# V1_0.net
KiCad netlist of a schematic drawn in Altium Designer
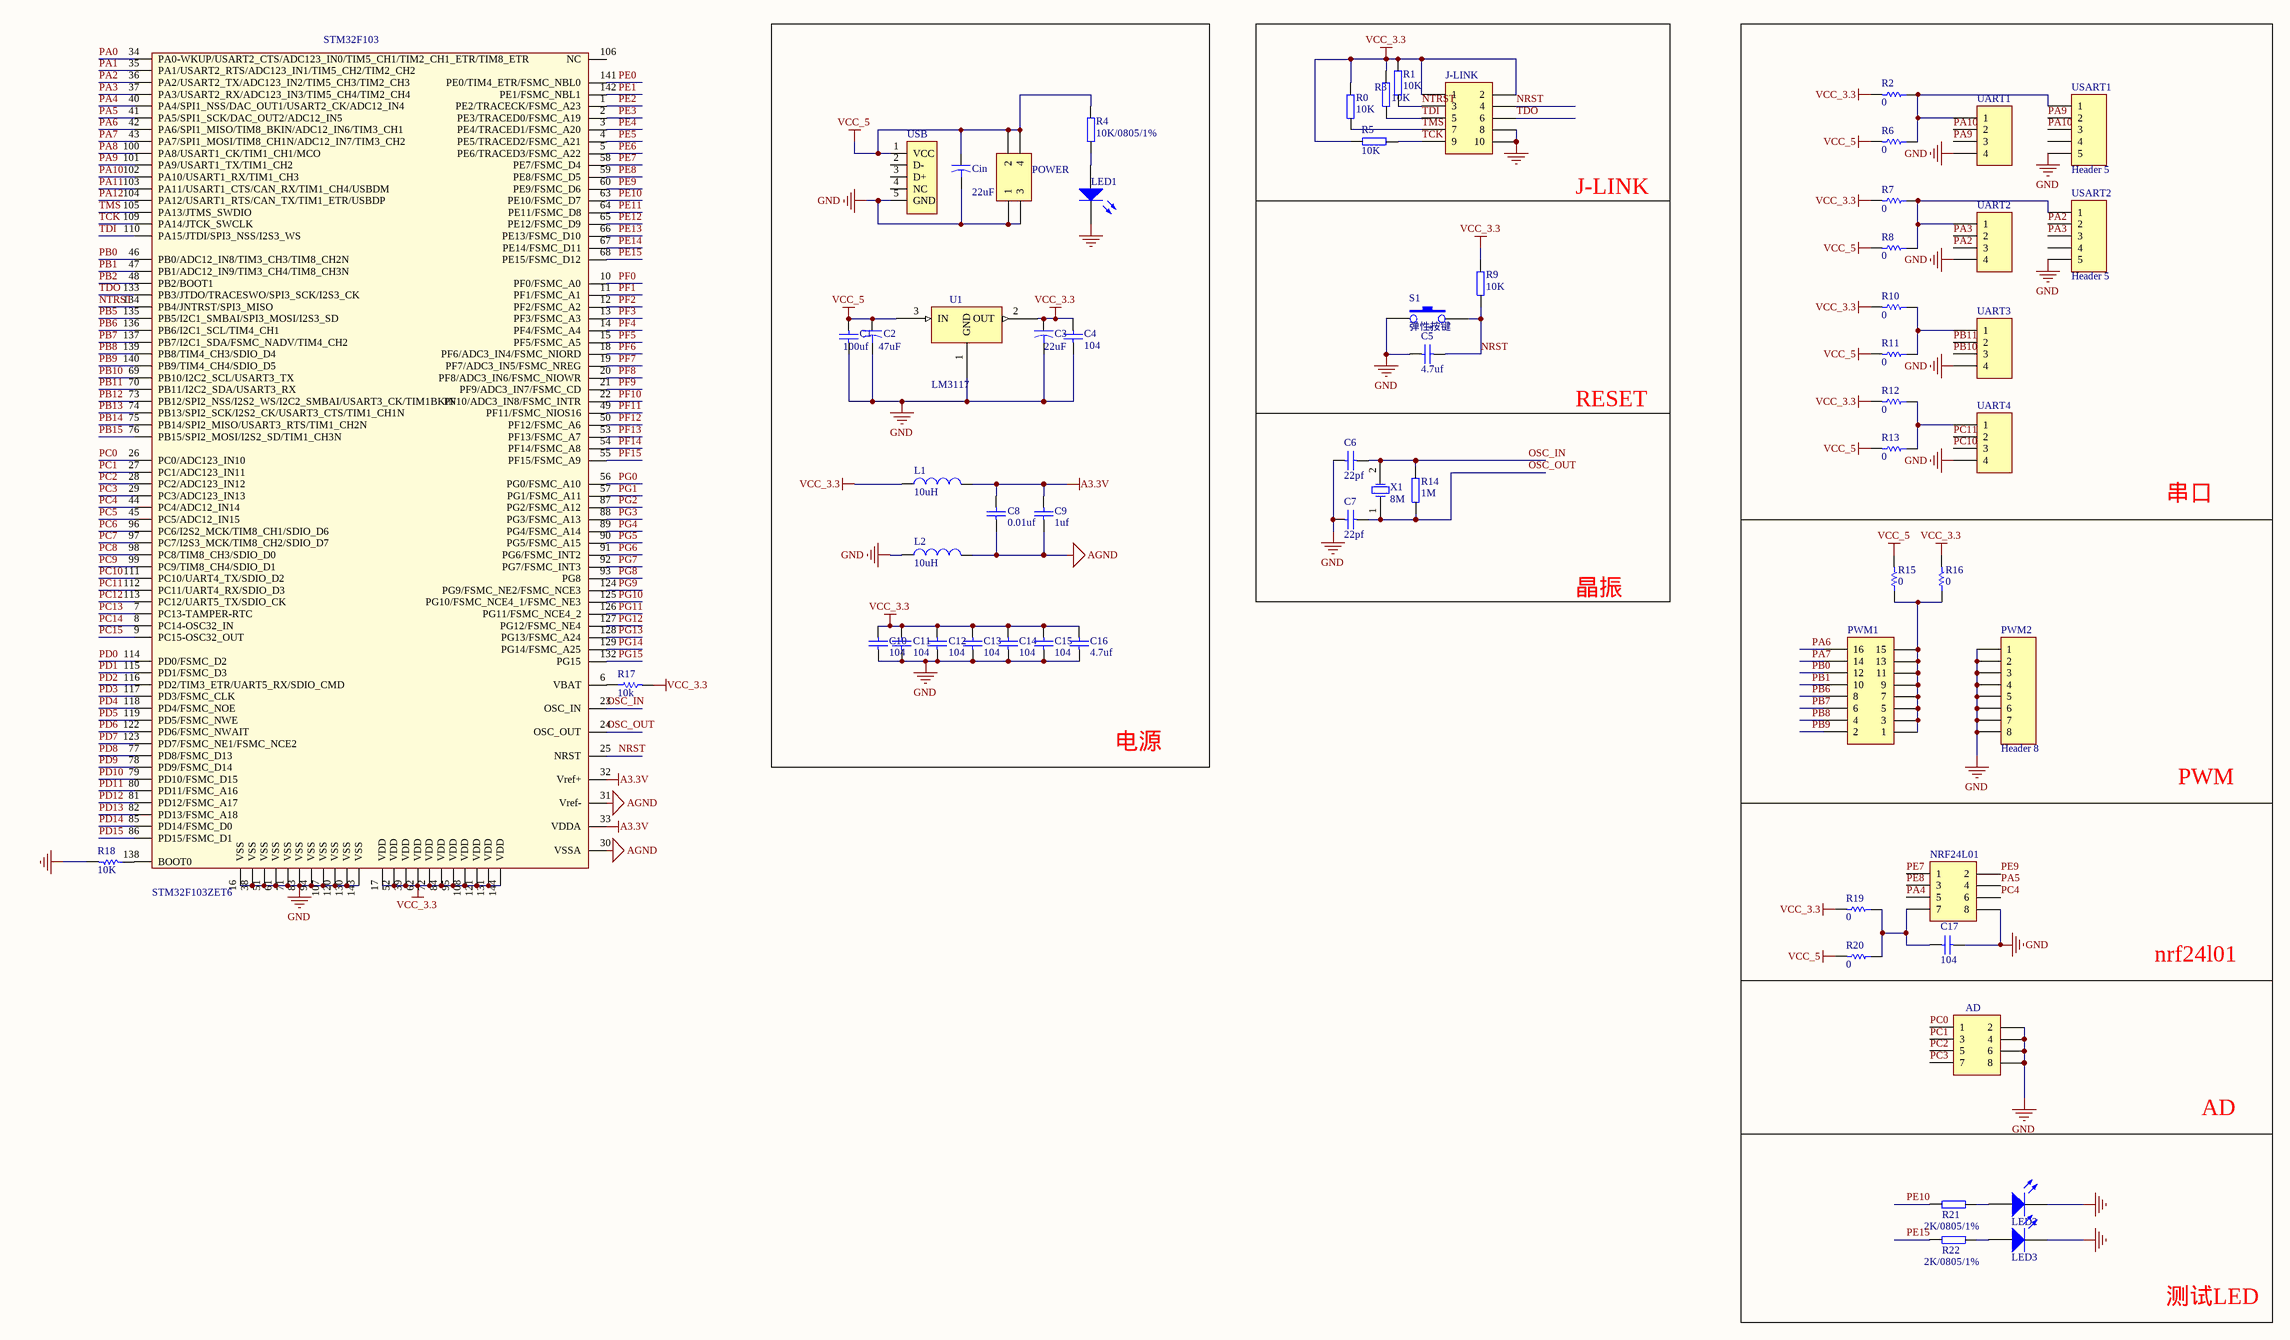
[diagram p0: 解析板V1.0.SchDoc]

(export (version "E")
  (design (tool "Eeschema 10.0.6"))
  (components
    (comp (ref "AD")
      (value "Header 4X2")
      (footprint "HDR2X4")
      (description "Header, 4-Pin, Dual row")
      (fields (field (name "PUBLISHER") "Altium Limited"))
      (libsource (lib "Miscellaneous Connectors") (part "Header 4X2"))
    )
    (comp (ref "C1")
      (value "100uf")
      (footprint "0805")
      (description "C0805")
      (fields (field (name "Comment") "0805"))
      (libsource (lib "MyLib") (part "Cap C0805"))
    )
    (comp (ref "C2")
      (value "47uF")
      (footprint "1812")
      (description "Capacitor")
      (fields (field (name "Comment") "Cap2") (field (name "PUBLISHER") "Altium Limited"))
      (libsource (lib "Miscellaneous Devices") (part "Cap2"))
    )
    (comp (ref "C3")
      (value "22uF")
      (footprint "1812")
      (description "Capacitor")
      (fields (field (name "Comment") "Cap2") (field (name "PUBLISHER") "Altium Limited"))
      (libsource (lib "Miscellaneous Devices") (part "Cap2"))
    )
    (comp (ref "C4")
      (value "104")
      (footprint "0805")
      (description "C0805")
      (fields (field (name "Comment") "0805"))
      (libsource (lib "MyLib") (part "Cap C0805"))
    )
    (comp (ref "C5")
      (value "4.7uf")
      (footprint "0805")
      (description "C0805")
      (fields (field (name "Comment") "0805"))
      (libsource (lib "MyLib") (part "Cap C0805"))
    )
    (comp (ref "C6")
      (value "22pf")
      (footprint "0805")
      (description "C0805")
      (fields (field (name "Comment") "0805"))
      (libsource (lib "MyLib") (part "Cap C0805"))
    )
    (comp (ref "C7")
      (value "22pf")
      (footprint "0805")
      (description "C0805")
      (fields (field (name "Comment") "0805"))
      (libsource (lib "MyLib") (part "Cap C0805"))
    )
    (comp (ref "C8")
      (value "0.01uf")
      (footprint "0805")
      (description "C0805")
      (fields (field (name "Comment") "0805"))
      (libsource (lib "MyLib") (part "Cap C0805"))
    )
    (comp (ref "C9")
      (value "1uf")
      (footprint "0805")
      (description "C0805")
      (fields (field (name "Comment") "0805"))
      (libsource (lib "MyLib") (part "Cap C0805"))
    )
    (comp (ref "C10")
      (value "104")
      (footprint "0805")
      (description "C0805")
      (fields (field (name "Comment") "0805"))
      (libsource (lib "MyLib") (part "Cap C0805"))
    )
    (comp (ref "C11")
      (value "104")
      (footprint "0805")
      (description "C0805")
      (fields (field (name "Comment") "0805"))
      (libsource (lib "MyLib") (part "Cap C0805"))
    )
    (comp (ref "C12")
      (value "104")
      (footprint "0805")
      (description "C0805")
      (fields (field (name "Comment") "0805"))
      (libsource (lib "MyLib") (part "Cap C0805"))
    )
    (comp (ref "C13")
      (value "104")
      (footprint "0805")
      (description "C0805")
      (fields (field (name "Comment") "0805"))
      (libsource (lib "MyLib") (part "Cap C0805"))
    )
    (comp (ref "C14")
      (value "104")
      (footprint "0805")
      (description "C0805")
      (fields (field (name "Comment") "0805"))
      (libsource (lib "MyLib") (part "Cap C0805"))
    )
    (comp (ref "C15")
      (value "104")
      (footprint "0805")
      (description "C0805")
      (fields (field (name "Comment") "0805"))
      (libsource (lib "MyLib") (part "Cap C0805"))
    )
    (comp (ref "C16")
      (value "4.7uf")
      (footprint "0805")
      (description "C0805")
      (fields (field (name "Comment") "0805"))
      (libsource (lib "MyLib") (part "Cap C0805"))
    )
    (comp (ref "C17")
      (value "104")
      (footprint "0805")
      (description "C0805")
      (fields (field (name "Comment") "0805"))
      (libsource (lib "MyLib") (part "Cap C0805"))
    )
    (comp (ref "Cin")
      (value "22uF")
      (footprint "1812")
      (description "Capacitor")
      (fields (field (name "Comment") "Cap2") (field (name "PUBLISHER") "Altium Limited"))
      (libsource (lib "Miscellaneous Devices") (part "Cap2"))
    )
    (comp (ref "J-LINK")
      (value "Header 5X2")
      (footprint "HDR2X5")
      (description "Header, 5-Pin, Dual row")
      (fields (field (name "PUBLISHER") "Altium Limited"))
      (libsource (lib "Miscellaneous Connectors") (part "Header 5X2"))
    )
    (comp (ref "L1")
      (value "10uH")
      (footprint "0805")
      (description "Inductor")
      (fields (field (name "PUBLISHER") "Altium Limited"))
      (libsource (lib "Miscellaneous Devices") (part "Inductor"))
    )
    (comp (ref "L2")
      (value "10uH")
      (footprint "0805")
      (description "Inductor")
      (fields (field (name "PUBLISHER") "Altium Limited"))
      (libsource (lib "Miscellaneous Devices") (part "Inductor"))
    )
    (comp (ref "LED1") (value "LED") (footprint "0805") (libsource (lib "K60") (part "LED")))
    (comp (ref "LED2") (value "LED") (footprint "0805") (libsource (lib "K60") (part "LED")))
    (comp (ref "LED3") (value "LED") (footprint "0805") (libsource (lib "K60") (part "LED")))
    (comp (ref "NRF24L01")
      (value "Header 4X2")
      (footprint "HDR2X4")
      (description "Header, 4-Pin, Dual row")
      (fields (field (name "PUBLISHER") "Altium Limited"))
      (libsource (lib "Miscellaneous Connectors") (part "Header 4X2"))
    )
    (comp (ref "POWER")
      (value "Header 2X2")
      (footprint "HDR2X2")
      (description "Header, 2-Pin, Dual row")
      (fields (field (name "PUBLISHER") "Altium Limited"))
      (libsource (lib "Miscellaneous Connectors") (part "Header 2X2"))
    )
    (comp (ref "PWM1")
      (value "Header 8X2")
      (footprint "HDR2X8")
      (description "Header, 8-Pin, Dual row")
      (fields (field (name "PUBLISHER") "Altium Limited"))
      (libsource (lib "Miscellaneous Connectors") (part "Header 8X2"))
    )
    (comp (ref "PWM2")
      (value "Header 8")
      (footprint "HDR1X8")
      (description "Header, 8-Pin")
      (fields (field (name "PUBLISHER") "Altium Limited"))
      (libsource (lib "Miscellaneous Connectors") (part "Header 8"))
    )
    (comp (ref "R0") (value "10K") (footprint "0805") (libsource (lib "*") (part "RES5")))
    (comp (ref "R1") (value "10K") (footprint "0805") (libsource (lib "*") (part "RES5")))
    (comp (ref "R2")
      (value "0")
      (footprint "0805")
      (description "Resistor")
      (fields (field (name "Comment") "Res1") (field (name "PUBLISHER") "Altium Limited"))
      (libsource (lib "Miscellaneous Devices") (part "Res1"))
    )
    (comp (ref "R3") (value "10K") (footprint "0805") (libsource (lib "*") (part "RES5")))
    (comp (ref "R4") (value "10K/0805/1%") (footprint "0805") (libsource (lib "*") (part "RES5")))
    (comp (ref "R5") (value "10K") (footprint "0805") (libsource (lib "*") (part "RES5")))
    (comp (ref "R6")
      (value "0")
      (footprint "0805")
      (description "Resistor")
      (fields (field (name "Comment") "Res1") (field (name "PUBLISHER") "Altium Limited"))
      (libsource (lib "Miscellaneous Devices") (part "Res1"))
    )
    (comp (ref "R7")
      (value "0")
      (footprint "0805")
      (description "Resistor")
      (fields (field (name "Comment") "Res1") (field (name "PUBLISHER") "Altium Limited"))
      (libsource (lib "Miscellaneous Devices") (part "Res1"))
    )
    (comp (ref "R8")
      (value "0")
      (footprint "0805")
      (description "Resistor")
      (fields (field (name "Comment") "Res1") (field (name "PUBLISHER") "Altium Limited"))
      (libsource (lib "Miscellaneous Devices") (part "Res1"))
    )
    (comp (ref "R9") (value "10K") (footprint "0805") (libsource (lib "*") (part "RES5")))
    (comp (ref "R10")
      (value "0")
      (footprint "0805")
      (description "Resistor")
      (fields (field (name "Comment") "Res1") (field (name "PUBLISHER") "Altium Limited"))
      (libsource (lib "Miscellaneous Devices") (part "Res1"))
    )
    (comp (ref "R11")
      (value "0")
      (footprint "0805")
      (description "Resistor")
      (fields (field (name "Comment") "Res1") (field (name "PUBLISHER") "Altium Limited"))
      (libsource (lib "Miscellaneous Devices") (part "Res1"))
    )
    (comp (ref "R12")
      (value "0")
      (footprint "0805")
      (description "Resistor")
      (fields (field (name "Comment") "Res1") (field (name "PUBLISHER") "Altium Limited"))
      (libsource (lib "Miscellaneous Devices") (part "Res1"))
    )
    (comp (ref "R13")
      (value "0")
      (footprint "0805")
      (description "Resistor")
      (fields (field (name "Comment") "Res1") (field (name "PUBLISHER") "Altium Limited"))
      (libsource (lib "Miscellaneous Devices") (part "Res1"))
    )
    (comp (ref "R14") (value "1M") (footprint "0805") (libsource (lib "*") (part "RES5")))
    (comp (ref "R15")
      (value "0")
      (footprint "0805")
      (description "Resistor")
      (fields (field (name "Comment") "Res1") (field (name "PUBLISHER") "Altium Limited"))
      (libsource (lib "Miscellaneous Devices") (part "Res1"))
    )
    (comp (ref "R16")
      (value "0")
      (footprint "0805")
      (description "Resistor")
      (fields (field (name "Comment") "Res1") (field (name "PUBLISHER") "Altium Limited"))
      (libsource (lib "Miscellaneous Devices") (part "Res1"))
    )
    (comp (ref "R17")
      (value "10k")
      (footprint "0805")
      (description "Resistor")
      (fields (field (name "Comment") "Res1") (field (name "PUBLISHER") "Altium Limited"))
      (libsource (lib "Miscellaneous Devices") (part "Res1"))
    )
    (comp (ref "R18")
      (value "10K")
      (footprint "0805")
      (description "Resistor")
      (fields (field (name "PUBLISHER") "Altium Limited"))
      (libsource (lib "*") (part "res1"))
    )
    (comp (ref "R19")
      (value "0")
      (footprint "0805")
      (description "Resistor")
      (fields (field (name "Comment") "Res1") (field (name "PUBLISHER") "Altium Limited"))
      (libsource (lib "Miscellaneous Devices") (part "Res1"))
    )
    (comp (ref "R20")
      (value "0")
      (footprint "0805")
      (description "Resistor")
      (fields (field (name "Comment") "Res1") (field (name "PUBLISHER") "Altium Limited"))
      (libsource (lib "Miscellaneous Devices") (part "Res1"))
    )
    (comp (ref "R21") (value "2K/0805/1%") (footprint "0805") (libsource (lib "*") (part "RES5")))
    (comp (ref "R22") (value "2K/0805/1%") (footprint "0805") (libsource (lib "*") (part "RES5")))
    (comp (ref "S1")
      (value "*")
      (footprint "按键开关（贴片）")
      (fields (field (name "COMM") "弹性按键"))
      (libsource (lib "Integrated_Library1") (part "单弹性按键"))
    )
    (comp (ref "STM32F103")
      (value "STM32F103ZET6")
      (footprint "LQFP144")
      (libsource (lib "WARSHIP") (part "STM32F103ZET6"))
    )
    (comp (ref "U1")
      (value "LM3117")
      (footprint "LM1117")
      (libsource (lib "Integrated_Library1") (part "LM1117"))
    )
    (comp (ref "UART1")
      (value "Header 4")
      (footprint "HDR1X4")
      (description "Header, 4-Pin")
      (fields (field (name "PUBLISHER") "Altium Limited"))
      (libsource (lib "Miscellaneous Connectors") (part "Header 4"))
    )
    (comp (ref "UART2")
      (value "Header 4")
      (footprint "HDR1X4")
      (description "Header, 4-Pin")
      (fields (field (name "PUBLISHER") "Altium Limited"))
      (libsource (lib "Miscellaneous Connectors") (part "Header 4"))
    )
    (comp (ref "UART3")
      (value "Header 4")
      (footprint "HDR1X4")
      (description "Header, 4-Pin")
      (fields (field (name "PUBLISHER") "Altium Limited"))
      (libsource (lib "Miscellaneous Connectors") (part "Header 4"))
    )
    (comp (ref "UART4")
      (value "Header 4")
      (footprint "HDR1X4")
      (description "Header, 4-Pin")
      (fields (field (name "PUBLISHER") "Altium Limited"))
      (libsource (lib "Miscellaneous Connectors") (part "Header 4"))
    )
    (comp (ref "USART1")
      (value "Header 5")
      (footprint "HDR1X5")
      (description "Header, 5-Pin")
      (fields (field (name "PUBLISHER") "Altium Limited"))
      (libsource (lib "Miscellaneous Connectors") (part "Header 5"))
    )
    (comp (ref "USART2")
      (value "Header 5")
      (footprint "HDR1X5")
      (description "Header, 5-Pin")
      (fields (field (name "PUBLISHER") "Altium Limited"))
      (libsource (lib "Miscellaneous Connectors") (part "Header 5"))
    )
    (comp (ref "USB") (value "USB-B(Mini)") (footprint "USB/SM0.8-6H5") (libsource (lib "原理图") (part "USB5")))
    (comp (ref "X1") (value "8M") (footprint "0.5-晶振") (libsource (lib "Integrated_Library1") (part "XTAL")))
  )
  (nets
    (net (code "1") (name "/NRST") (class "Default")
      (node (ref "C5") (pin "1") (pinfunction "1_1") (pintype "passive"))
      (node (ref "J-LINK") (pin "4") (pinfunction "4_4") (pintype "passive"))
      (node (ref "R9") (pin "1") (pintype "passive"))
      (node (ref "S1") (pin "2") (pinfunction "2_2") (pintype "passive"))
      (node (ref "STM32F103") (pin "25") (pinfunction "NRST_25") (pintype "passive"))
    )
    (net (code "2") (name "/NTRST") (class "Default")
      (node (ref "J-LINK") (pin "3") (pinfunction "3_3") (pintype "passive"))
      (node (ref "R1") (pin "1") (pintype "passive"))
      (node (ref "STM32F103") (pin "134") (pinfunction "PB4/JNTRST/SPI3_MISO_134") (pintype "passive"))
    )
    (net (code "3") (name "/OSC_IN") (class "Default")
      (node (ref "C6") (pin "1") (pinfunction "1_1") (pintype "passive"))
      (node (ref "R14") (pin "2") (pintype "passive"))
      (node (ref "STM32F103") (pin "23") (pinfunction "OSC_IN_23") (pintype "passive"))
      (node (ref "X1") (pin "2") (pinfunction "OSC2_2") (pintype "passive"))
    )
    (net (code "4") (name "/OSC_OUT") (class "Default")
      (node (ref "C7") (pin "1") (pinfunction "1_1") (pintype "passive"))
      (node (ref "R14") (pin "1") (pintype "passive"))
      (node (ref "STM32F103") (pin "24") (pinfunction "OSC_OUT_24") (pintype "passive"))
      (node (ref "X1") (pin "1") (pinfunction "OSC1_1") (pintype "passive"))
    )
    (net (code "5") (name "/PA0") (class "Default")
      (node (ref "STM32F103") (pin "34") (pinfunction "PA0-WKUP/USART2_CTS/ADC123_IN0/TIM5_CH1/TIM2_CH1_ETR/TIM8_ETR_34") (pintype "passive"))
    )
    (net (code "6") (name "/PA1") (class "Default")
      (node (ref "STM32F103") (pin "35") (pinfunction "PA1/USART2_RTS/ADC123_IN1/TIM5_CH2/TIM2_CH2_35") (pintype "passive"))
    )
    (net (code "7") (name "/PA2") (class "Default")
      (node (ref "STM32F103") (pin "36") (pinfunction "PA2/USART2_TX/ADC123_IN2/TIM5_CH3/TIM2_CH3_36") (pintype "passive"))
      (node (ref "UART2") (pin "3") (pinfunction "3_3") (pintype "passive"))
      (node (ref "USART2") (pin "2") (pinfunction "2_2") (pintype "passive"))
    )
    (net (code "8") (name "/PA3") (class "Default")
      (node (ref "STM32F103") (pin "37") (pinfunction "PA3/USART2_RX/ADC123_IN3/TIM5_CH4/TIM2_CH4_37") (pintype "passive"))
      (node (ref "UART2") (pin "2") (pinfunction "2_2") (pintype "passive"))
      (node (ref "USART2") (pin "3") (pinfunction "3_3") (pintype "passive"))
    )
    (net (code "9") (name "/PA4") (class "Default")
      (node (ref "NRF24L01") (pin "5") (pinfunction "5_5") (pintype "passive"))
      (node (ref "STM32F103") (pin "40") (pinfunction "PA4/SPI1_NSS/DAC_OUT1/USART2_CK/ADC12_IN4_40") (pintype "passive"))
    )
    (net (code "10") (name "/PA5") (class "Default")
      (node (ref "NRF24L01") (pin "4") (pinfunction "4_4") (pintype "passive"))
      (node (ref "STM32F103") (pin "41") (pinfunction "PA5/SPI1_SCK/DAC_OUT2/ADC12_IN5_41") (pintype "passive"))
    )
    (net (code "11") (name "/PA6") (class "Default")
      (node (ref "PWM1") (pin "16") (pinfunction "16_16") (pintype "passive"))
      (node (ref "STM32F103") (pin "42") (pinfunction "PA6/SPI1_MISO/TIM8_BKIN/ADC12_IN6/TIM3_CH1_42") (pintype "passive"))
    )
    (net (code "12") (name "/PA7") (class "Default")
      (node (ref "PWM1") (pin "14") (pinfunction "14_14") (pintype "passive"))
      (node (ref "STM32F103") (pin "43") (pinfunction "PA7/SPI1_MOSI/TIM8_CH1N/ADC12_IN7/TIM3_CH2_43") (pintype "passive"))
    )
    (net (code "13") (name "/PA8") (class "Default")
      (node (ref "STM32F103") (pin "100") (pinfunction "PA8/USART1_CK/TIM1_CH1/MCO_100") (pintype "passive"))
    )
    (net (code "14") (name "/PA9") (class "Default")
      (node (ref "STM32F103") (pin "101") (pinfunction "PA9/USART1_TX/TIM1_CH2_101") (pintype "passive"))
      (node (ref "UART1") (pin "3") (pinfunction "3_3") (pintype "passive"))
      (node (ref "USART1") (pin "2") (pinfunction "2_2") (pintype "passive"))
    )
    (net (code "15") (name "/PA10") (class "Default")
      (node (ref "STM32F103") (pin "102") (pinfunction "PA10/USART1_RX/TIM1_CH3_102") (pintype "passive"))
      (node (ref "UART1") (pin "2") (pinfunction "2_2") (pintype "passive"))
      (node (ref "USART1") (pin "3") (pinfunction "3_3") (pintype "passive"))
    )
    (net (code "16") (name "/PA11") (class "Default")
      (node (ref "STM32F103") (pin "103") (pinfunction "PA11/USART1_CTS/CAN_RX/TIM1_CH4/USBDM_103") (pintype "passive"))
    )
    (net (code "17") (name "/PA12") (class "Default")
      (node (ref "STM32F103") (pin "104") (pinfunction "PA12/USART1_RTS/CAN_TX/TIM1_ETR/USBDP_104") (pintype "passive"))
    )
    (net (code "18") (name "/PB0") (class "Default")
      (node (ref "PWM1") (pin "12") (pinfunction "12_12") (pintype "passive"))
      (node (ref "STM32F103") (pin "46") (pinfunction "PB0/ADC12_IN8/TIM3_CH3/TIM8_CH2N_46") (pintype "passive"))
    )
    (net (code "19") (name "/PB1") (class "Default")
      (node (ref "PWM1") (pin "10") (pinfunction "10_10") (pintype "passive"))
      (node (ref "STM32F103") (pin "47") (pinfunction "PB1/ADC12_IN9/TIM3_CH4/TIM8_CH3N_47") (pintype "passive"))
    )
    (net (code "20") (name "/PB2") (class "Default")
      (node (ref "STM32F103") (pin "48") (pinfunction "PB2/BOOT1_48") (pintype "passive"))
    )
    (net (code "21") (name "/PB5") (class "Default")
      (node (ref "STM32F103") (pin "135") (pinfunction "PB5/I2C1_SMBAI/SPI3_MOSI/I2S3_SD_135") (pintype "passive"))
    )
    (net (code "22") (name "/PB6") (class "Default")
      (node (ref "PWM1") (pin "8") (pinfunction "8_8") (pintype "passive"))
      (node (ref "STM32F103") (pin "136") (pinfunction "PB6/I2C1_SCL/TIM4_CH1_136") (pintype "passive"))
    )
    (net (code "23") (name "/PB7") (class "Default")
      (node (ref "PWM1") (pin "6") (pinfunction "6_6") (pintype "passive"))
      (node (ref "STM32F103") (pin "137") (pinfunction "PB7/I2C1_SDA/FSMC_NADV/TIM4_CH2_137") (pintype "passive"))
    )
    (net (code "24") (name "/PB8") (class "Default")
      (node (ref "PWM1") (pin "4") (pinfunction "4_4") (pintype "passive"))
      (node (ref "STM32F103") (pin "139") (pinfunction "PB8/TIM4_CH3/SDIO_D4_139") (pintype "passive"))
    )
    (net (code "25") (name "/PB9") (class "Default")
      (node (ref "PWM1") (pin "2") (pinfunction "2_2") (pintype "passive"))
      (node (ref "STM32F103") (pin "140") (pinfunction "PB9/TIM4_CH4/SDIO_D5_140") (pintype "passive"))
    )
    (net (code "26") (name "/PB10") (class "Default")
      (node (ref "STM32F103") (pin "69") (pinfunction "PB10/I2C2_SCL/USART3_TX_69") (pintype "passive"))
      (node (ref "UART3") (pin "3") (pinfunction "3_3") (pintype "passive"))
    )
    (net (code "27") (name "/PB11") (class "Default")
      (node (ref "STM32F103") (pin "70") (pinfunction "PB11/I2C2_SDA/USART3_RX_70") (pintype "passive"))
      (node (ref "UART3") (pin "2") (pinfunction "2_2") (pintype "passive"))
    )
    (net (code "28") (name "/PB12") (class "Default")
      (node (ref "STM32F103") (pin "73") (pinfunction "PB12/SPI2_NSS/I2S2_WS/I2C2_SMBAI/USART3_CK/TIM1BKIN_73") (pintype "passive"))
    )
    (net (code "29") (name "/PB13") (class "Default")
      (node (ref "STM32F103") (pin "74") (pinfunction "PB13/SPI2_SCK/I2S2_CK/USART3_CTS/TIM1_CH1N_74") (pintype "passive"))
    )
    (net (code "30") (name "/PB14") (class "Default")
      (node (ref "STM32F103") (pin "75") (pinfunction "PB14/SPI2_MISO/USART3_RTS/TIM1_CH2N_75") (pintype "passive"))
    )
    (net (code "31") (name "/PB15") (class "Default")
      (node (ref "STM32F103") (pin "76") (pinfunction "PB15/SPI2_MOSI/I2S2_SD/TIM1_CH3N_76") (pintype "passive"))
    )
    (net (code "32") (name "/PC0") (class "Default")
      (node (ref "AD") (pin "1") (pinfunction "1_1") (pintype "passive"))
      (node (ref "STM32F103") (pin "26") (pinfunction "PC0/ADC123_IN10_26") (pintype "passive"))
    )
    (net (code "33") (name "/PC1") (class "Default")
      (node (ref "AD") (pin "3") (pinfunction "3_3") (pintype "passive"))
      (node (ref "STM32F103") (pin "27") (pinfunction "PC1/ADC123_IN11_27") (pintype "passive"))
    )
    (net (code "34") (name "/PC2") (class "Default")
      (node (ref "AD") (pin "5") (pinfunction "5_5") (pintype "passive"))
      (node (ref "STM32F103") (pin "28") (pinfunction "PC2/ADC123_IN12_28") (pintype "passive"))
    )
    (net (code "35") (name "/PC3") (class "Default")
      (node (ref "AD") (pin "7") (pinfunction "7_7") (pintype "passive"))
      (node (ref "STM32F103") (pin "29") (pinfunction "PC3/ADC123_IN13_29") (pintype "passive"))
    )
    (net (code "36") (name "/PC4") (class "Default")
      (node (ref "NRF24L01") (pin "6") (pinfunction "6_6") (pintype "passive"))
      (node (ref "STM32F103") (pin "44") (pinfunction "PC4/ADC12_IN14_44") (pintype "passive"))
    )
    (net (code "37") (name "/PC5") (class "Default")
      (node (ref "STM32F103") (pin "45") (pinfunction "PC5/ADC12_IN15_45") (pintype "passive"))
    )
    (net (code "38") (name "/PC6") (class "Default")
      (node (ref "STM32F103") (pin "96") (pinfunction "PC6/I2S2_MCK/TIM8_CH1/SDIO_D6_96") (pintype "passive"))
    )
    (net (code "39") (name "/PC7") (class "Default")
      (node (ref "STM32F103") (pin "97") (pinfunction "PC7/I2S3_MCK/TIM8_CH2/SDIO_D7_97") (pintype "passive"))
    )
    (net (code "40") (name "/PC8") (class "Default")
      (node (ref "STM32F103") (pin "98") (pinfunction "PC8/TIM8_CH3/SDIO_D0_98") (pintype "passive"))
    )
    (net (code "41") (name "/PC9") (class "Default")
      (node (ref "STM32F103") (pin "99") (pinfunction "PC9/TIM8_CH4/SDIO_D1_99") (pintype "passive"))
    )
    (net (code "42") (name "/PC10") (class "Default")
      (node (ref "STM32F103") (pin "111") (pinfunction "PC10/UART4_TX/SDIO_D2_111") (pintype "passive"))
      (node (ref "UART4") (pin "3") (pinfunction "3_3") (pintype "passive"))
    )
    (net (code "43") (name "/PC11") (class "Default")
      (node (ref "STM32F103") (pin "112") (pinfunction "PC11/UART4_RX/SDIO_D3_112") (pintype "passive"))
      (node (ref "UART4") (pin "2") (pinfunction "2_2") (pintype "passive"))
    )
    (net (code "44") (name "/PC12") (class "Default")
      (node (ref "STM32F103") (pin "113") (pinfunction "PC12/UART5_TX/SDIO_CK_113") (pintype "passive"))
    )
    (net (code "45") (name "/PC13") (class "Default")
      (node (ref "STM32F103") (pin "7") (pinfunction "PC13-TAMPER-RTC_7") (pintype "passive"))
    )
    (net (code "46") (name "/PC14") (class "Default")
      (node (ref "STM32F103") (pin "8") (pinfunction "PC14-OSC32_IN_8") (pintype "passive"))
    )
    (net (code "47") (name "/PC15") (class "Default")
      (node (ref "STM32F103") (pin "9") (pinfunction "PC15-OSC32_OUT_9") (pintype "passive"))
    )
    (net (code "48") (name "/PD0") (class "Default")
      (node (ref "STM32F103") (pin "114") (pinfunction "PD0/FSMC_D2_114") (pintype "passive"))
    )
    (net (code "49") (name "/PD1") (class "Default")
      (node (ref "STM32F103") (pin "115") (pinfunction "PD1/FSMC_D3_115") (pintype "passive"))
    )
    (net (code "50") (name "/PD2") (class "Default")
      (node (ref "STM32F103") (pin "116") (pinfunction "PD2/TIM3_ETR/UART5_RX/SDIO_CMD_116") (pintype "passive"))
    )
    (net (code "51") (name "/PD3") (class "Default")
      (node (ref "STM32F103") (pin "117") (pinfunction "PD3/FSMC_CLK_117") (pintype "passive"))
    )
    (net (code "52") (name "/PD4") (class "Default")
      (node (ref "STM32F103") (pin "118") (pinfunction "PD4/FSMC_NOE_118") (pintype "passive"))
    )
    (net (code "53") (name "/PD5") (class "Default")
      (node (ref "STM32F103") (pin "119") (pinfunction "PD5/FSMC_NWE_119") (pintype "passive"))
    )
    (net (code "54") (name "/PD6") (class "Default")
      (node (ref "STM32F103") (pin "122") (pinfunction "PD6/FSMC_NWAIT_122") (pintype "passive"))
    )
    (net (code "55") (name "/PD7") (class "Default")
      (node (ref "STM32F103") (pin "123") (pinfunction "PD7/FSMC_NE1/FSMC_NCE2_123") (pintype "passive"))
    )
    (net (code "56") (name "/PD8") (class "Default")
      (node (ref "STM32F103") (pin "77") (pinfunction "PD8/FSMC_D13_77") (pintype "passive"))
    )
    (net (code "57") (name "/PD9") (class "Default")
      (node (ref "STM32F103") (pin "78") (pinfunction "PD9/FSMC_D14_78") (pintype "passive"))
    )
    (net (code "58") (name "/PD10") (class "Default")
      (node (ref "STM32F103") (pin "79") (pinfunction "PD10/FSMC_D15_79") (pintype "passive"))
    )
    (net (code "59") (name "/PD11") (class "Default")
      (node (ref "STM32F103") (pin "80") (pinfunction "PD11/FSMC_A16_80") (pintype "passive"))
    )
    (net (code "60") (name "/PD12") (class "Default")
      (node (ref "STM32F103") (pin "81") (pinfunction "PD12/FSMC_A17_81") (pintype "passive"))
    )
    (net (code "61") (name "/PD13") (class "Default")
      (node (ref "STM32F103") (pin "82") (pinfunction "PD13/FSMC_A18_82") (pintype "passive"))
    )
    (net (code "62") (name "/PD14") (class "Default")
      (node (ref "STM32F103") (pin "85") (pinfunction "PD14/FSMC_D0_85") (pintype "passive"))
    )
    (net (code "63") (name "/PD15") (class "Default")
      (node (ref "STM32F103") (pin "86") (pinfunction "PD15/FSMC_D1_86") (pintype "passive"))
    )
    (net (code "64") (name "/PE0") (class "Default")
      (node (ref "STM32F103") (pin "141") (pinfunction "PE0/TIM4_ETR/FSMC_NBL0_141") (pintype "passive"))
    )
    (net (code "65") (name "/PE1") (class "Default")
      (node (ref "STM32F103") (pin "142") (pinfunction "PE1/FSMC_NBL1_142") (pintype "passive"))
    )
    (net (code "66") (name "/PE2") (class "Default")
      (node (ref "STM32F103") (pin "1") (pinfunction "PE2/TRACECK/FSMC_A23_1") (pintype "passive"))
    )
    (net (code "67") (name "/PE3") (class "Default")
      (node (ref "STM32F103") (pin "2") (pinfunction "PE3/TRACED0/FSMC_A19_2") (pintype "passive"))
    )
    (net (code "68") (name "/PE4") (class "Default")
      (node (ref "STM32F103") (pin "3") (pinfunction "PE4/TRACED1/FSMC_A20_3") (pintype "passive"))
    )
    (net (code "69") (name "/PE5") (class "Default")
      (node (ref "STM32F103") (pin "4") (pinfunction "PE5/TRACED2/FSMC_A21_4") (pintype "passive"))
    )
    (net (code "70") (name "/PE6") (class "Default")
      (node (ref "STM32F103") (pin "5") (pinfunction "PE6/TRACED3/FSMC_A22_5") (pintype "passive"))
    )
    (net (code "71") (name "/PE7") (class "Default")
      (node (ref "NRF24L01") (pin "1") (pinfunction "1_1") (pintype "passive"))
      (node (ref "STM32F103") (pin "58") (pinfunction "PE7/FSMC_D4_58") (pintype "passive"))
    )
    (net (code "72") (name "/PE8") (class "Default")
      (node (ref "NRF24L01") (pin "3") (pinfunction "3_3") (pintype "passive"))
      (node (ref "STM32F103") (pin "59") (pinfunction "PE8/FSMC_D5_59") (pintype "passive"))
    )
    (net (code "73") (name "/PE9") (class "Default")
      (node (ref "NRF24L01") (pin "2") (pinfunction "2_2") (pintype "passive"))
      (node (ref "STM32F103") (pin "60") (pinfunction "PE9/FSMC_D6_60") (pintype "passive"))
    )
    (net (code "74") (name "/PE10") (class "Default")
      (node (ref "R21") (pin "1") (pintype "passive"))
      (node (ref "STM32F103") (pin "63") (pinfunction "PE10/FSMC_D7_63") (pintype "passive"))
    )
    (net (code "75") (name "/PE11") (class "Default")
      (node (ref "STM32F103") (pin "64") (pinfunction "PE11/FSMC_D8_64") (pintype "passive"))
    )
    (net (code "76") (name "/PE12") (class "Default")
      (node (ref "STM32F103") (pin "65") (pinfunction "PE12/FSMC_D9_65") (pintype "passive"))
    )
    (net (code "77") (name "/PE13") (class "Default")
      (node (ref "STM32F103") (pin "66") (pinfunction "PE13/FSMC_D10_66") (pintype "passive"))
    )
    (net (code "78") (name "/PE14") (class "Default")
      (node (ref "STM32F103") (pin "67") (pinfunction "PE14/FSMC_D11_67") (pintype "passive"))
    )
    (net (code "79") (name "/PE15") (class "Default")
      (node (ref "R22") (pin "1") (pintype "passive"))
      (node (ref "STM32F103") (pin "68") (pinfunction "PE15/FSMC_D12_68") (pintype "passive"))
    )
    (net (code "80") (name "/PF0") (class "Default")
      (node (ref "STM32F103") (pin "10") (pinfunction "PF0/FSMC_A0_10") (pintype "passive"))
    )
    (net (code "81") (name "/PF1") (class "Default")
      (node (ref "STM32F103") (pin "11") (pinfunction "PF1/FSMC_A1_11") (pintype "passive"))
    )
    (net (code "82") (name "/PF2") (class "Default")
      (node (ref "STM32F103") (pin "12") (pinfunction "PF2/FSMC_A2_12") (pintype "passive"))
    )
    (net (code "83") (name "/PF3") (class "Default")
      (node (ref "STM32F103") (pin "13") (pinfunction "PF3/FSMC_A3_13") (pintype "passive"))
    )
    (net (code "84") (name "/PF4") (class "Default")
      (node (ref "STM32F103") (pin "14") (pinfunction "PF4/FSMC_A4_14") (pintype "passive"))
    )
    (net (code "85") (name "/PF5") (class "Default")
      (node (ref "STM32F103") (pin "15") (pinfunction "PF5/FSMC_A5_15") (pintype "passive"))
    )
    (net (code "86") (name "/PF6") (class "Default")
      (node (ref "STM32F103") (pin "18") (pinfunction "PF6/ADC3_IN4/FSMC_NIORD_18") (pintype "passive"))
    )
    (net (code "87") (name "/PF7") (class "Default")
      (node (ref "STM32F103") (pin "19") (pinfunction "PF7/ADC3_IN5/FSMC_NREG_19") (pintype "passive"))
    )
    (net (code "88") (name "/PF8") (class "Default")
      (node (ref "STM32F103") (pin "20") (pinfunction "PF8/ADC3_IN6/FSMC_NIOWR_20") (pintype "passive"))
    )
    (net (code "89") (name "/PF9") (class "Default")
      (node (ref "STM32F103") (pin "21") (pinfunction "PF9/ADC3_IN7/FSMC_CD_21") (pintype "passive"))
    )
    (net (code "90") (name "/PF10") (class "Default")
      (node (ref "STM32F103") (pin "22") (pinfunction "PF10/ADC3_IN8/FSMC_INTR_22") (pintype "passive"))
    )
    (net (code "91") (name "/PF11") (class "Default")
      (node (ref "STM32F103") (pin "49") (pinfunction "PF11/FSMC_NIOS16_49") (pintype "passive"))
    )
    (net (code "92") (name "/PF12") (class "Default")
      (node (ref "STM32F103") (pin "50") (pinfunction "PF12/FSMC_A6_50") (pintype "passive"))
    )
    (net (code "93") (name "/PF13") (class "Default")
      (node (ref "STM32F103") (pin "53") (pinfunction "PF13/FSMC_A7_53") (pintype "passive"))
    )
    (net (code "94") (name "/PF14") (class "Default")
      (node (ref "STM32F103") (pin "54") (pinfunction "PF14/FSMC_A8_54") (pintype "passive"))
    )
    (net (code "95") (name "/PF15") (class "Default")
      (node (ref "STM32F103") (pin "55") (pinfunction "PF15/FSMC_A9_55") (pintype "passive"))
    )
    (net (code "96") (name "/PG0") (class "Default")
      (node (ref "STM32F103") (pin "56") (pinfunction "PG0/FSMC_A10_56") (pintype "passive"))
    )
    (net (code "97") (name "/PG1") (class "Default")
      (node (ref "STM32F103") (pin "57") (pinfunction "PG1/FSMC_A11_57") (pintype "passive"))
    )
    (net (code "98") (name "/PG2") (class "Default")
      (node (ref "STM32F103") (pin "87") (pinfunction "PG2/FSMC_A12_87") (pintype "passive"))
    )
    (net (code "99") (name "/PG3") (class "Default")
      (node (ref "STM32F103") (pin "88") (pinfunction "PG3/FSMC_A13_88") (pintype "passive"))
    )
    (net (code "100") (name "/PG4") (class "Default")
      (node (ref "STM32F103") (pin "89") (pinfunction "PG4/FSMC_A14_89") (pintype "passive"))
    )
    (net (code "101") (name "/PG5") (class "Default")
      (node (ref "STM32F103") (pin "90") (pinfunction "PG5/FSMC_A15_90") (pintype "passive"))
    )
    (net (code "102") (name "/PG6") (class "Default")
      (node (ref "STM32F103") (pin "91") (pinfunction "PG6/FSMC_INT2_91") (pintype "passive"))
    )
    (net (code "103") (name "/PG7") (class "Default")
      (node (ref "STM32F103") (pin "92") (pinfunction "PG7/FSMC_INT3_92") (pintype "passive"))
    )
    (net (code "104") (name "/PG8") (class "Default")
      (node (ref "STM32F103") (pin "93") (pinfunction "PG8_93") (pintype "passive"))
    )
    (net (code "105") (name "/PG9") (class "Default")
      (node (ref "STM32F103") (pin "124") (pinfunction "PG9/FSMC_NE2/FSMC_NCE3_124") (pintype "passive"))
    )
    (net (code "106") (name "/PG10") (class "Default")
      (node (ref "STM32F103") (pin "125") (pinfunction "PG10/FSMC_NCE4_1/FSMC_NE3_125") (pintype "passive"))
    )
    (net (code "107") (name "/PG11") (class "Default")
      (node (ref "STM32F103") (pin "126") (pinfunction "PG11/FSMC_NCE4_2_126") (pintype "passive"))
    )
    (net (code "108") (name "/PG12") (class "Default")
      (node (ref "STM32F103") (pin "127") (pinfunction "PG12/FSMC_NE4_127") (pintype "passive"))
    )
    (net (code "109") (name "/PG13") (class "Default")
      (node (ref "STM32F103") (pin "128") (pinfunction "PG13/FSMC_A24_128") (pintype "passive"))
    )
    (net (code "110") (name "/PG14") (class "Default")
      (node (ref "STM32F103") (pin "129") (pinfunction "PG14/FSMC_A25_129") (pintype "passive"))
    )
    (net (code "111") (name "/PG15") (class "Default")
      (node (ref "STM32F103") (pin "132") (pinfunction "PG15_132") (pintype "passive"))
    )
    (net (code "112") (name "/TCK") (class "Default")
      (node (ref "J-LINK") (pin "9") (pinfunction "9_9") (pintype "passive"))
      (node (ref "R5") (pin "1") (pintype "passive"))
      (node (ref "STM32F103") (pin "109") (pinfunction "PA14/JTCK_SWCLK_109") (pintype "passive"))
    )
    (net (code "113") (name "/TDI") (class "Default")
      (node (ref "J-LINK") (pin "5") (pinfunction "5_5") (pintype "passive"))
      (node (ref "R3") (pin "1") (pintype "passive"))
      (node (ref "STM32F103") (pin "110") (pinfunction "PA15/JTDI/SPI3_NSS/I2S3_WS_110") (pintype "passive"))
    )
    (net (code "114") (name "/TDO") (class "Default")
      (node (ref "J-LINK") (pin "6") (pinfunction "6_6") (pintype "passive"))
      (node (ref "STM32F103") (pin "133") (pinfunction "PB3/JTDO/TRACESWO/SPI3_SCK/I2S3_CK_133") (pintype "passive"))
    )
    (net (code "115") (name "/TMS") (class "Default")
      (node (ref "J-LINK") (pin "7") (pinfunction "7_7") (pintype "passive"))
      (node (ref "R0") (pin "1") (pintype "passive"))
      (node (ref "STM32F103") (pin "105") (pinfunction "PA13/JTMS_SWDIO_105") (pintype "passive"))
    )
    (net (code "116") (name "A3.3V") (class "Default")
      (node (ref "C8") (pin "1") (pinfunction "1_1") (pintype "passive"))
      (node (ref "C9") (pin "1") (pinfunction "1_1") (pintype "passive"))
      (node (ref "L1") (pin "2") (pinfunction "2_2") (pintype "passive"))
      (node (ref "STM32F103") (pin "32") (pinfunction "Vref+_32") (pintype "passive"))
      (node (ref "STM32F103") (pin "33") (pinfunction "VDDA_33") (pintype "passive"))
    )
    (net (code "117") (name "AGND") (class "Default")
      (node (ref "C8") (pin "2") (pinfunction "2_2") (pintype "passive"))
      (node (ref "C9") (pin "2") (pinfunction "2_2") (pintype "passive"))
      (node (ref "L2") (pin "2") (pinfunction "2_2") (pintype "passive"))
      (node (ref "STM32F103") (pin "30") (pinfunction "VSSA_30") (pintype "passive"))
      (node (ref "STM32F103") (pin "31") (pinfunction "Vref-_31") (pintype "passive"))
    )
    (net (code "118") (name "GND") (class "Default")
      (node (ref "AD") (pin "2") (pinfunction "2_2") (pintype "passive"))
      (node (ref "AD") (pin "4") (pinfunction "4_4") (pintype "passive"))
      (node (ref "AD") (pin "6") (pinfunction "6_6") (pintype "passive"))
      (node (ref "AD") (pin "8") (pinfunction "8_8") (pintype "passive"))
      (node (ref "C1") (pin "1") (pinfunction "1_1") (pintype "passive"))
      (node (ref "C10") (pin "2") (pinfunction "2_2") (pintype "passive"))
      (node (ref "C11") (pin "2") (pinfunction "2_2") (pintype "passive"))
      (node (ref "C12") (pin "2") (pinfunction "2_2") (pintype "passive"))
      (node (ref "C13") (pin "2") (pinfunction "2_2") (pintype "passive"))
      (node (ref "C14") (pin "2") (pinfunction "2_2") (pintype "passive"))
      (node (ref "C15") (pin "2") (pinfunction "2_2") (pintype "passive"))
      (node (ref "C16") (pin "2") (pinfunction "2_2") (pintype "passive"))
      (node (ref "C17") (pin "2") (pinfunction "2_2") (pintype "passive"))
      (node (ref "C2") (pin "2") (pinfunction "2_2") (pintype "passive"))
      (node (ref "C3") (pin "2") (pinfunction "2_2") (pintype "passive"))
      (node (ref "C4") (pin "1") (pinfunction "1_1") (pintype "passive"))
      (node (ref "C5") (pin "2") (pinfunction "2_2") (pintype "passive"))
      (node (ref "C6") (pin "2") (pinfunction "2_2") (pintype "passive"))
      (node (ref "C7") (pin "2") (pinfunction "2_2") (pintype "passive"))
      (node (ref "Cin") (pin "2") (pinfunction "2_2") (pintype "passive"))
      (node (ref "J-LINK") (pin "10") (pinfunction "10_10") (pintype "passive"))
      (node (ref "J-LINK") (pin "8") (pinfunction "8_8") (pintype "passive"))
      (node (ref "L2") (pin "1") (pinfunction "1_1") (pintype "passive"))
      (node (ref "LED1") (pin "2") (pinfunction "K_2") (pintype "passive"))
      (node (ref "LED2") (pin "2") (pinfunction "K_2") (pintype "passive"))
      (node (ref "LED3") (pin "2") (pinfunction "K_2") (pintype "passive"))
      (node (ref "NRF24L01") (pin "8") (pinfunction "8_8") (pintype "passive"))
      (node (ref "POWER") (pin "1") (pinfunction "1_1") (pintype "passive"))
      (node (ref "POWER") (pin "3") (pinfunction "3_3") (pintype "passive"))
      (node (ref "PWM2") (pin "1") (pinfunction "1_1") (pintype "passive"))
      (node (ref "PWM2") (pin "2") (pinfunction "2_2") (pintype "passive"))
      (node (ref "PWM2") (pin "3") (pinfunction "3_3") (pintype "passive"))
      (node (ref "PWM2") (pin "4") (pinfunction "4_4") (pintype "passive"))
      (node (ref "PWM2") (pin "5") (pinfunction "5_5") (pintype "passive"))
      (node (ref "PWM2") (pin "6") (pinfunction "6_6") (pintype "passive"))
      (node (ref "PWM2") (pin "7") (pinfunction "7_7") (pintype "passive"))
      (node (ref "PWM2") (pin "8") (pinfunction "8_8") (pintype "passive"))
      (node (ref "R18") (pin "2") (pinfunction "2_2") (pintype "passive"))
      (node (ref "S1") (pin "1") (pinfunction "1_1") (pintype "passive"))
      (node (ref "STM32F103") (pin "107") (pinfunction "VSS_107") (pintype "passive"))
      (node (ref "STM32F103") (pin "120") (pinfunction "VSS_120") (pintype "passive"))
      (node (ref "STM32F103") (pin "130") (pinfunction "VSS_130") (pintype "passive"))
      (node (ref "STM32F103") (pin "143") (pinfunction "VSS_143") (pintype "passive"))
      (node (ref "STM32F103") (pin "16") (pinfunction "VSS_16") (pintype "passive"))
      (node (ref "STM32F103") (pin "38") (pinfunction "VSS_38") (pintype "passive"))
      (node (ref "STM32F103") (pin "51") (pinfunction "VSS_51") (pintype "passive"))
      (node (ref "STM32F103") (pin "61") (pinfunction "VSS_61") (pintype "passive"))
      (node (ref "STM32F103") (pin "71") (pinfunction "VSS_71") (pintype "passive"))
      (node (ref "STM32F103") (pin "83") (pinfunction "VSS_83") (pintype "passive"))
      (node (ref "STM32F103") (pin "94") (pinfunction "VSS_94") (pintype "passive"))
      (node (ref "U1") (pin "1") (pinfunction "GND_1") (pintype "passive"))
      (node (ref "UART1") (pin "4") (pinfunction "4_4") (pintype "passive"))
      (node (ref "UART2") (pin "4") (pinfunction "4_4") (pintype "passive"))
      (node (ref "UART3") (pin "4") (pinfunction "4_4") (pintype "passive"))
      (node (ref "UART4") (pin "4") (pinfunction "4_4") (pintype "passive"))
      (node (ref "USART1") (pin "5") (pinfunction "5_5") (pintype "passive"))
      (node (ref "USART2") (pin "5") (pinfunction "5_5") (pintype "passive"))
      (node (ref "USB") (pin "5") (pinfunction "GND_5") (pintype "passive"))
    )
    (net (code "119") (name "Net-(C17-Pad1)") (class "Default")
      (node (ref "C17") (pin "1") (pinfunction "1_1") (pintype "passive"))
      (node (ref "NRF24L01") (pin "7") (pinfunction "7_7") (pintype "passive"))
      (node (ref "R19") (pin "1") (pinfunction "1_1") (pintype "passive"))
      (node (ref "R20") (pin "1") (pinfunction "1_1") (pintype "passive"))
    )
    (net (code "120") (name "Net-(LED1-A)") (class "Default")
      (node (ref "LED1") (pin "1") (pinfunction "A_1") (pintype "passive"))
      (node (ref "R4") (pin "2") (pintype "passive"))
    )
    (net (code "121") (name "Net-(LED2-A)") (class "Default")
      (node (ref "LED2") (pin "1") (pinfunction "A_1") (pintype "passive"))
      (node (ref "R21") (pin "2") (pintype "passive"))
    )
    (net (code "122") (name "Net-(LED3-A)") (class "Default")
      (node (ref "LED3") (pin "1") (pinfunction "A_1") (pintype "passive"))
      (node (ref "R22") (pin "2") (pintype "passive"))
    )
    (net (code "123") (name "Net-(PWM1-Pad1)") (class "Default")
      (node (ref "PWM1") (pin "1") (pinfunction "1_1") (pintype "passive"))
      (node (ref "PWM1") (pin "11") (pinfunction "11_11") (pintype "passive"))
      (node (ref "PWM1") (pin "13") (pinfunction "13_13") (pintype "passive"))
      (node (ref "PWM1") (pin "15") (pinfunction "15_15") (pintype "passive"))
      (node (ref "PWM1") (pin "3") (pinfunction "3_3") (pintype "passive"))
      (node (ref "PWM1") (pin "5") (pinfunction "5_5") (pintype "passive"))
      (node (ref "PWM1") (pin "7") (pinfunction "7_7") (pintype "passive"))
      (node (ref "PWM1") (pin "9") (pinfunction "9_9") (pintype "passive"))
      (node (ref "R15") (pin "1") (pinfunction "1_1") (pintype "passive"))
      (node (ref "R16") (pin "1") (pinfunction "1_1") (pintype "passive"))
    )
    (net (code "124") (name "Net-(R2-Pad1)") (class "Default")
      (node (ref "R2") (pin "1") (pinfunction "1_1") (pintype "passive"))
      (node (ref "R6") (pin "1") (pinfunction "1_1") (pintype "passive"))
      (node (ref "UART1") (pin "1") (pinfunction "1_1") (pintype "passive"))
      (node (ref "USART1") (pin "1") (pinfunction "1_1") (pintype "passive"))
    )
    (net (code "125") (name "Net-(R7-Pad1)") (class "Default")
      (node (ref "R7") (pin "1") (pinfunction "1_1") (pintype "passive"))
      (node (ref "R8") (pin "1") (pinfunction "1_1") (pintype "passive"))
      (node (ref "UART2") (pin "1") (pinfunction "1_1") (pintype "passive"))
      (node (ref "USART2") (pin "1") (pinfunction "1_1") (pintype "passive"))
    )
    (net (code "126") (name "Net-(R10-Pad1)") (class "Default")
      (node (ref "R10") (pin "1") (pinfunction "1_1") (pintype "passive"))
      (node (ref "R11") (pin "1") (pinfunction "1_1") (pintype "passive"))
      (node (ref "UART3") (pin "1") (pinfunction "1_1") (pintype "passive"))
    )
    (net (code "127") (name "Net-(R12-Pad1)") (class "Default")
      (node (ref "R12") (pin "1") (pinfunction "1_1") (pintype "passive"))
      (node (ref "R13") (pin "1") (pinfunction "1_1") (pintype "passive"))
      (node (ref "UART4") (pin "1") (pinfunction "1_1") (pintype "passive"))
    )
    (net (code "128") (name "Net-(STM32F103-BOOT0)") (class "Default")
      (node (ref "R18") (pin "1") (pinfunction "1_1") (pintype "passive"))
      (node (ref "STM32F103") (pin "138") (pinfunction "BOOT0_138") (pintype "passive"))
    )
    (net (code "129") (name "Net-(STM32F103-VBAT)") (class "Default")
      (node (ref "R17") (pin "1") (pinfunction "1_1") (pintype "passive"))
      (node (ref "STM32F103") (pin "6") (pinfunction "VBAT_6") (pintype "passive"))
    )
    (net (code "130") (name "VCC_3.3") (class "Default")
      (node (ref "C10") (pin "1") (pinfunction "1_1") (pintype "passive"))
      (node (ref "C11") (pin "1") (pinfunction "1_1") (pintype "passive"))
      (node (ref "C12") (pin "1") (pinfunction "1_1") (pintype "passive"))
      (node (ref "C13") (pin "1") (pinfunction "1_1") (pintype "passive"))
      (node (ref "C14") (pin "1") (pinfunction "1_1") (pintype "passive"))
      (node (ref "C15") (pin "1") (pinfunction "1_1") (pintype "passive"))
      (node (ref "C16") (pin "1") (pinfunction "1_1") (pintype "passive"))
      (node (ref "C3") (pin "1") (pinfunction "1_1") (pintype "passive"))
      (node (ref "C4") (pin "2") (pinfunction "2_2") (pintype "passive"))
      (node (ref "J-LINK") (pin "1") (pinfunction "1_1") (pintype "passive"))
      (node (ref "J-LINK") (pin "2") (pinfunction "2_2") (pintype "passive"))
      (node (ref "L1") (pin "1") (pinfunction "1_1") (pintype "passive"))
      (node (ref "R0") (pin "2") (pintype "passive"))
      (node (ref "R1") (pin "2") (pintype "passive"))
      (node (ref "R10") (pin "2") (pinfunction "2_2") (pintype "passive"))
      (node (ref "R12") (pin "2") (pinfunction "2_2") (pintype "passive"))
      (node (ref "R16") (pin "2") (pinfunction "2_2") (pintype "passive"))
      (node (ref "R17") (pin "2") (pinfunction "2_2") (pintype "passive"))
      (node (ref "R19") (pin "2") (pinfunction "2_2") (pintype "passive"))
      (node (ref "R2") (pin "2") (pinfunction "2_2") (pintype "passive"))
      (node (ref "R3") (pin "2") (pintype "passive"))
      (node (ref "R5") (pin "2") (pintype "passive"))
      (node (ref "R7") (pin "2") (pinfunction "2_2") (pintype "passive"))
      (node (ref "R9") (pin "2") (pintype "passive"))
      (node (ref "STM32F103") (pin "108") (pinfunction "VDD_108") (pintype "passive"))
      (node (ref "STM32F103") (pin "121") (pinfunction "VDD_121") (pintype "passive"))
      (node (ref "STM32F103") (pin "131") (pinfunction "VDD_131") (pintype "passive"))
      (node (ref "STM32F103") (pin "144") (pinfunction "VDD_144") (pintype "passive"))
      (node (ref "STM32F103") (pin "17") (pinfunction "VDD_17") (pintype "passive"))
      (node (ref "STM32F103") (pin "39") (pinfunction "VDD_39") (pintype "passive"))
      (node (ref "STM32F103") (pin "52") (pinfunction "VDD_52") (pintype "passive"))
      (node (ref "STM32F103") (pin "62") (pinfunction "VDD_62") (pintype "passive"))
      (node (ref "STM32F103") (pin "72") (pinfunction "VDD_72") (pintype "passive"))
      (node (ref "STM32F103") (pin "84") (pinfunction "VDD_84") (pintype "passive"))
      (node (ref "STM32F103") (pin "95") (pinfunction "VDD_95") (pintype "passive"))
      (node (ref "U1") (pin "2") (pinfunction "OUT_2") (pintype "output"))
    )
    (net (code "131") (name "VCC_5") (class "Default")
      (node (ref "C1") (pin "2") (pinfunction "2_2") (pintype "passive"))
      (node (ref "C2") (pin "1") (pinfunction "1_1") (pintype "passive"))
      (node (ref "Cin") (pin "1") (pinfunction "1_1") (pintype "passive"))
      (node (ref "POWER") (pin "2") (pinfunction "2_2") (pintype "passive"))
      (node (ref "POWER") (pin "4") (pinfunction "4_4") (pintype "passive"))
      (node (ref "R11") (pin "2") (pinfunction "2_2") (pintype "passive"))
      (node (ref "R13") (pin "2") (pinfunction "2_2") (pintype "passive"))
      (node (ref "R15") (pin "2") (pinfunction "2_2") (pintype "passive"))
      (node (ref "R20") (pin "2") (pinfunction "2_2") (pintype "passive"))
      (node (ref "R4") (pin "1") (pintype "passive"))
      (node (ref "R6") (pin "2") (pinfunction "2_2") (pintype "passive"))
      (node (ref "R8") (pin "2") (pinfunction "2_2") (pintype "passive"))
      (node (ref "U1") (pin "3") (pinfunction "IN_3") (pintype "input"))
      (node (ref "USB") (pin "1") (pinfunction "VCC_1") (pintype "passive"))
    )
    (net (code "132") (name "unconnected-(STM32F103-NC-Pad106)") (class "Default")
      (node (ref "STM32F103") (pin "106") (pinfunction "NC_106") (pintype "passive"))
    )
    (net (code "133") (name "unconnected-(USART1-Pad4)") (class "Default")
      (node (ref "USART1") (pin "4") (pinfunction "4_4") (pintype "passive"))
    )
    (net (code "134") (name "unconnected-(USART2-Pad4)") (class "Default")
      (node (ref "USART2") (pin "4") (pinfunction "4_4") (pintype "passive"))
    )
    (net (code "135") (name "unconnected-(USB-D+-Pad3)") (class "Default")
      (node (ref "USB") (pin "3") (pinfunction "D+_3") (pintype "passive"))
    )
    (net (code "136") (name "unconnected-(USB-D--Pad2)") (class "Default")
      (node (ref "USB") (pin "2") (pinfunction "D-_2") (pintype "passive"))
    )
    (net (code "137") (name "unconnected-(USB-NC-Pad4)") (class "Default")
      (node (ref "USB") (pin "4") (pinfunction "NC_4") (pintype "passive"))
    )
  )
)
